# ha_notchecker.net
KiCad netlist of a schematic drawn in EAGLE
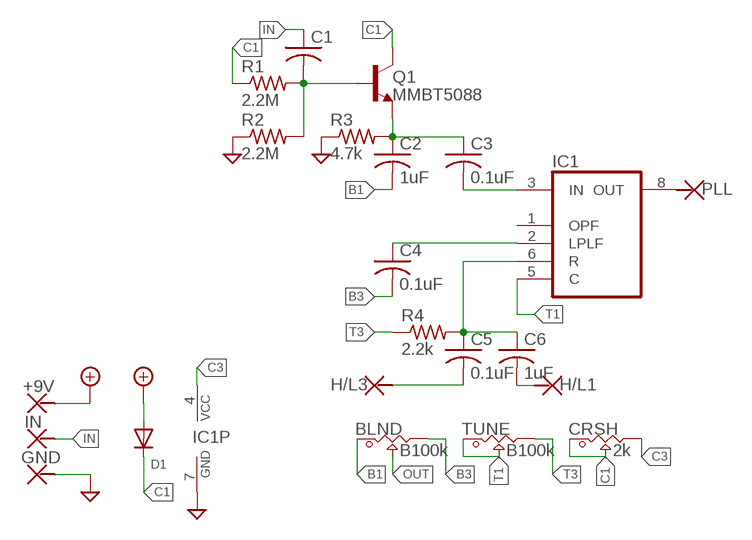
[diagram p0: schematic, sheet 1]

(export (version "E")
  (design (tool "Eeschema 10.0.6"))
  (components
    (comp (ref "+9V")
      (value "PAD")
      (footprint "eagle-import:PAD")
      (libsource (lib "eagle-import") (part "PAD"))
    )
    (comp (ref "BLND")
      (value "B100k")
      (footprint "eagle-import:POT_9MM_SMD")
      (libsource (lib "eagle-import") (part "POT_9MM_SMD"))
    )
    (comp (ref "C1")
      (value "C-USC0603")
      (footprint "eagle-import:C0603")
      (libsource (lib "eagle-import") (part "C-USC0603"))
    )
    (comp (ref "C2")
      (value "1uF")
      (footprint "eagle-import:C0603")
      (libsource (lib "eagle-import") (part "C-USC0603"))
    )
    (comp (ref "C3")
      (value "0.1uF")
      (footprint "eagle-import:C0603")
      (libsource (lib "eagle-import") (part "C-USC0603"))
    )
    (comp (ref "C4")
      (value "0.1uF")
      (footprint "eagle-import:C0603")
      (libsource (lib "eagle-import") (part "C-USC0603"))
    )
    (comp (ref "C5")
      (value "0.1uF")
      (footprint "eagle-import:C0603")
      (libsource (lib "eagle-import") (part "C-USC0603"))
    )
    (comp (ref "C6")
      (value "1uF")
      (footprint "eagle-import:C0603")
      (libsource (lib "eagle-import") (part "C-USC0603"))
    )
    (comp (ref "CRSH")
      (value "2k")
      (footprint "eagle-import:POT_9MM_SMD")
      (libsource (lib "eagle-import") (part "POT_9MM_SMD"))
    )
    (comp (ref "D1")
      (value "DIODESOD-123")
      (footprint "eagle-import:SOD-123")
      (libsource (lib "eagle-import") (part "DIODESOD-123"))
    )
    (comp (ref "GND")
      (value "PAD")
      (footprint "eagle-import:PAD")
      (libsource (lib "eagle-import") (part "PAD"))
    )
    (comp (ref "H/L1")
      (value "PAD")
      (footprint "eagle-import:PAD")
      (libsource (lib "eagle-import") (part "PAD"))
    )
    (comp (ref "H/L3")
      (value "PAD")
      (footprint "eagle-import:PAD")
      (libsource (lib "eagle-import") (part "PAD"))
    )
    (comp (ref "IC1")
      (value "XR-567K")
      (footprint "eagle-import:JSOP-08")
      (libsource (lib "eagle-import") (part "XR-567K"))
    )
    (comp (ref "IN")
      (value "PAD")
      (footprint "eagle-import:PAD")
      (libsource (lib "eagle-import") (part "PAD"))
    )
    (comp (ref "PLL")
      (value "PAD")
      (footprint "eagle-import:PAD")
      (libsource (lib "eagle-import") (part "PAD"))
    )
    (comp (ref "Q1")
      (value "MMBT5088")
      (footprint "eagle-import:SOT23-BEC")
      (fields (field (name "MF") "ON Semiconductor"))
      (libsource (lib "eagle-import") (part "MMBT5088"))
    )
    (comp (ref "R1")
      (value "2.2M")
      (footprint "eagle-import:R0603")
      (libsource (lib "eagle-import") (part "R-US_R0603"))
    )
    (comp (ref "R2")
      (value "2.2M")
      (footprint "eagle-import:R0603")
      (libsource (lib "eagle-import") (part "R-US_R0603"))
    )
    (comp (ref "R3")
      (value "4.7k")
      (footprint "eagle-import:R0603")
      (libsource (lib "eagle-import") (part "R-US_R0603"))
    )
    (comp (ref "R4")
      (value "2.2k")
      (footprint "eagle-import:R0603")
      (libsource (lib "eagle-import") (part "R-US_R0603"))
    )
    (comp (ref "TUNE")
      (value "B100k")
      (footprint "eagle-import:POT_9MM_SMD")
      (libsource (lib "eagle-import") (part "POT_9MM_SMD"))
    )
  )
  (nets
    (net (code "1") (name "+9V") (class "Default")
      (node (ref "+9V") (pin "P$1") (pinfunction "P$1_P$1") (pintype "bidirectional"))
      (node (ref "D1") (pin "A") (pinfunction "A_A") (pintype "passive"))
    )
    (net (code "2") (name "B1") (class "Default")
      (node (ref "BLND") (pin "1") (pinfunction "1_1") (pintype "bidirectional"))
      (node (ref "C2") (pin "2") (pinfunction "2_2") (pintype "passive"))
    )
    (net (code "3") (name "B3") (class "Default")
      (node (ref "BLND") (pin "3") (pinfunction "3_3") (pintype "bidirectional"))
      (node (ref "C4") (pin "2") (pinfunction "2_2") (pintype "passive"))
    )
    (net (code "4") (name "C1") (class "Default")
      (node (ref "CRSH") (pin "1") (pinfunction "1_1") (pintype "bidirectional"))
      (node (ref "CRSH") (pin "2") (pinfunction "2_2") (pintype "bidirectional"))
      (node (ref "D1") (pin "C") (pinfunction "C_C") (pintype "passive"))
      (node (ref "Q1") (pin "C") (pinfunction "C_C") (pintype "passive"))
      (node (ref "R1") (pin "1") (pinfunction "1_1") (pintype "passive"))
    )
    (net (code "5") (name "C3") (class "Default")
      (node (ref "CRSH") (pin "3") (pinfunction "3_3") (pintype "bidirectional"))
      (node (ref "IC1") (pin "4") (pinfunction "VCC_4") (pintype "power_in"))
    )
    (net (code "6") (name "GND") (class "Default")
      (node (ref "GND") (pin "P$1") (pinfunction "P$1_P$1") (pintype "bidirectional"))
      (node (ref "IC1") (pin "7") (pinfunction "GND_7") (pintype "power_in"))
      (node (ref "R2") (pin "1") (pinfunction "1_1") (pintype "passive"))
      (node (ref "R3") (pin "1") (pinfunction "1_1") (pintype "passive"))
    )
    (net (code "7") (name "IN") (class "Default")
      (node (ref "C1") (pin "1") (pinfunction "1_1") (pintype "passive"))
      (node (ref "IN") (pin "P$1") (pinfunction "P$1_P$1") (pintype "bidirectional"))
    )
    (net (code "8") (name "Net-(C1-Pad2)") (class "Default")
      (node (ref "C1") (pin "2") (pinfunction "2_2") (pintype "passive"))
      (node (ref "Q1") (pin "B") (pinfunction "B_B") (pintype "passive"))
      (node (ref "R1") (pin "2") (pinfunction "2_2") (pintype "passive"))
      (node (ref "R2") (pin "2") (pinfunction "2_2") (pintype "passive"))
    )
    (net (code "9") (name "Net-(C2-Pad1)") (class "Default")
      (node (ref "C2") (pin "1") (pinfunction "1_1") (pintype "passive"))
      (node (ref "C3") (pin "1") (pinfunction "1_1") (pintype "passive"))
      (node (ref "Q1") (pin "E") (pinfunction "E_E") (pintype "passive"))
      (node (ref "R3") (pin "2") (pinfunction "2_2") (pintype "passive"))
    )
    (net (code "10") (name "Net-(C5-Pad2)") (class "Default")
      (node (ref "C5") (pin "2") (pinfunction "2_2") (pintype "passive"))
      (node (ref "H/L3") (pin "P$1") (pinfunction "P$1_P$1") (pintype "bidirectional"))
    )
    (net (code "11") (name "Net-(C6-Pad2)") (class "Default")
      (node (ref "C6") (pin "2") (pinfunction "2_2") (pintype "passive"))
      (node (ref "H/L1") (pin "P$1") (pinfunction "P$1_P$1") (pintype "bidirectional"))
    )
    (net (code "12") (name "Net-(IC1A-IN)") (class "Default")
      (node (ref "C3") (pin "2") (pinfunction "2_2") (pintype "passive"))
      (node (ref "IC1") (pin "3") (pinfunction "IN_3") (pintype "input"))
    )
    (net (code "13") (name "Net-(IC1A-LPLF)") (class "Default")
      (node (ref "C4") (pin "1") (pinfunction "1_1") (pintype "passive"))
      (node (ref "IC1") (pin "2") (pinfunction "LPLF_2") (pintype "input"))
    )
    (net (code "14") (name "Net-(IC1A-OUT)") (class "Default")
      (node (ref "IC1") (pin "8") (pinfunction "OUT_8") (pintype "output"))
      (node (ref "PLL") (pin "P$1") (pinfunction "P$1_P$1") (pintype "bidirectional"))
    )
    (net (code "15") (name "Net-(IC1A-R)") (class "Default")
      (node (ref "C5") (pin "1") (pinfunction "1_1") (pintype "passive"))
      (node (ref "C6") (pin "1") (pinfunction "1_1") (pintype "passive"))
      (node (ref "IC1") (pin "6") (pinfunction "R_6") (pintype "input"))
      (node (ref "R4") (pin "2") (pinfunction "2_2") (pintype "passive"))
    )
    (net (code "16") (name "OUT") (class "Default")
      (node (ref "BLND") (pin "2") (pinfunction "2_2") (pintype "bidirectional"))
    )
    (net (code "17") (name "T1") (class "Default")
      (node (ref "IC1") (pin "5") (pinfunction "C_5") (pintype "input"))
      (node (ref "TUNE") (pin "1") (pinfunction "1_1") (pintype "bidirectional"))
      (node (ref "TUNE") (pin "2") (pinfunction "2_2") (pintype "bidirectional"))
    )
    (net (code "18") (name "T3") (class "Default")
      (node (ref "R4") (pin "1") (pinfunction "1_1") (pintype "passive"))
      (node (ref "TUNE") (pin "3") (pinfunction "3_3") (pintype "bidirectional"))
    )
    (net (code "19") (name "unconnected-(IC1A-OPF-Pad1)") (class "Default")
      (node (ref "IC1") (pin "1") (pinfunction "OPF_1") (pintype "input"))
    )
  )
)
